# PLD_Flash-Memory.net
KiCad netlist of a schematic drawn in Altium Designer
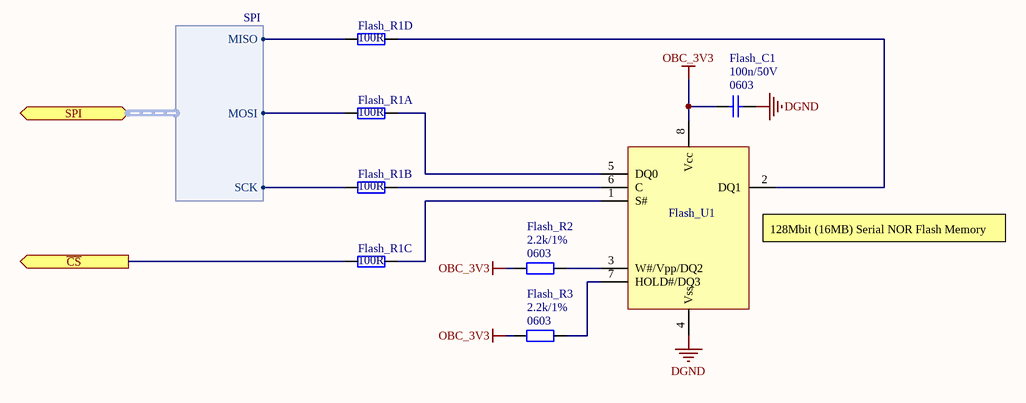
[diagram p0: PLD_Flash-Memory.SchDoc]

(export (version "E")
  (design (tool "Eeschema 10.0.6"))
  (components
    (comp (ref "Flash_C1")
      (value "100n/50V")
      (footprint "SMD_Capacitor_0603")
      (description "Ceramic Cap Kemet COTS 100n/50V X7R 0603")
      (fields
        (field (name "MANUFACTURER") "Kemet")
        (field (name "MANUFACTURERPARTNUMBER") "C0603T104K5RALTU")
        (field (name "PACKAGE") "0603")
      )
      (libsource (lib "capacitors") (part "Cer_C0603T104K5RALTU"))
    )
    (comp (ref "Flash_R1")
      (value "100R")
      (footprint "SMD_RESISTOR_ARRAY_YC124")
      (description "RESISTOR ARRAY, 4 x 0402")
      (libsource (lib "resistors") (part "4ResPack"))
    )
    (comp (ref "Flash_R2")
      (value "2.2k/1%")
      (footprint "SMD_Resistor_0603")
      (description "2.2k/1% Vishay CRCW 0603 Resistor. 100mW, 100ppm, 75V.")
      (fields
        (field (name "MANUFACTURERPARTNUMBER") "CRCW06032K20FKxxxx")
        (field (name "MANUFACTURER") "Vishay")
        (field (name "PACKAGE") "0603")
      )
      (libsource (lib "resistors") (part "CRCW06032K20FKxxxx"))
    )
    (comp (ref "Flash_R3")
      (value "2.2k/1%")
      (footprint "SMD_Resistor_0603")
      (description "2.2k/1% Vishay CRCW 0603 Resistor. 100mW, 100ppm, 75V.")
      (fields
        (field (name "MANUFACTURERPARTNUMBER") "CRCW06032K20FKxxxx")
        (field (name "MANUFACTURER") "Vishay")
        (field (name "PACKAGE") "0603")
      )
      (libsource (lib "resistors") (part "CRCW06032K20FKxxxx"))
    )
    (comp (ref "Flash_U1")
      (value "~")
      (footprint "DIP8 ADAPTER")
      (description "128Mbit, 3V Serial NOR Flash Memory")
      (fields
        (field (name "MANUFACTURER") "Micron")
        (field (name "MANUFACTURERPARTNUMBER") "N25Q128A13ESE40G")
      )
      (libsource (lib "microcircuits") (part "N25Q128A13ESE40G"))
    )
  )
  (nets
    (net (code "2") (name "/MISO") (class "Default")
      (node (ref "Flash_R1") (pin "5") (pinfunction "5_5") (pintype "passive"))
    )
    (net (code "3") (name "/MOSI") (class "Default")
      (node (ref "Flash_R1") (pin "8") (pinfunction "8_8") (pintype "passive"))
    )
    (net (code "4") (name "/SCK") (class "Default")
      (node (ref "Flash_R1") (pin "7") (pinfunction "7_7") (pintype "passive"))
    )
    (net (code "6") (name "/~{CS}") (class "Default")
      (node (ref "Flash_R1") (pin "6") (pinfunction "6_6") (pintype "passive"))
    )
    (net (code "7") (name "DGND") (class "Default")
      (node (ref "Flash_C1") (pin "1") (pinfunction "1_1") (pintype "passive"))
      (node (ref "Flash_U1") (pin "4") (pinfunction "Vss_4") (pintype "passive"))
    )
    (net (code "8") (name "Net-(Flash_U1-C)") (class "Default")
      (node (ref "Flash_R1") (pin "2") (pinfunction "2_2") (pintype "passive"))
      (node (ref "Flash_U1") (pin "6") (pinfunction "C_6") (pintype "passive"))
    )
    (net (code "9") (name "Net-(Flash_U1-DQ0)") (class "Default")
      (node (ref "Flash_R1") (pin "1") (pinfunction "1_1") (pintype "passive"))
      (node (ref "Flash_U1") (pin "5") (pinfunction "DQ0_5") (pintype "passive"))
    )
    (net (code "10") (name "Net-(Flash_U1-DQ1)") (class "Default")
      (node (ref "Flash_R1") (pin "4") (pinfunction "4_4") (pintype "passive"))
      (node (ref "Flash_U1") (pin "2") (pinfunction "DQ1_2") (pintype "passive"))
    )
    (net (code "11") (name "Net-(Flash_U1-HOLD#{slash}DQ3)") (class "Default")
      (node (ref "Flash_R3") (pin "1") (pinfunction "1_1") (pintype "passive"))
      (node (ref "Flash_U1") (pin "7") (pinfunction "HOLD#/DQ3_7") (pintype "passive"))
    )
    (net (code "12") (name "Net-(Flash_U1-S#)") (class "Default")
      (node (ref "Flash_R1") (pin "3") (pinfunction "3_3") (pintype "passive"))
      (node (ref "Flash_U1") (pin "1") (pinfunction "S#_1") (pintype "passive"))
    )
    (net (code "13") (name "Net-(Flash_U1-W#{slash}Vpp{slash}DQ2)") (class "Default")
      (node (ref "Flash_R2") (pin "1") (pinfunction "1_1") (pintype "passive"))
      (node (ref "Flash_U1") (pin "3") (pinfunction "W#/Vpp/DQ2_3") (pintype "passive"))
    )
    (net (code "14") (name "OBC_3V3") (class "Default")
      (node (ref "Flash_C1") (pin "2") (pinfunction "2_2") (pintype "passive"))
      (node (ref "Flash_R2") (pin "2") (pinfunction "2_2") (pintype "passive"))
      (node (ref "Flash_R3") (pin "2") (pinfunction "2_2") (pintype "passive"))
      (node (ref "Flash_U1") (pin "8") (pinfunction "Vcc_8") (pintype "passive"))
    )
  )
)
